# SCH_Ethernet_Based_PCB_Desiging_2026-05-.net
KiCad netlist of a schematic drawn in EasyEDA
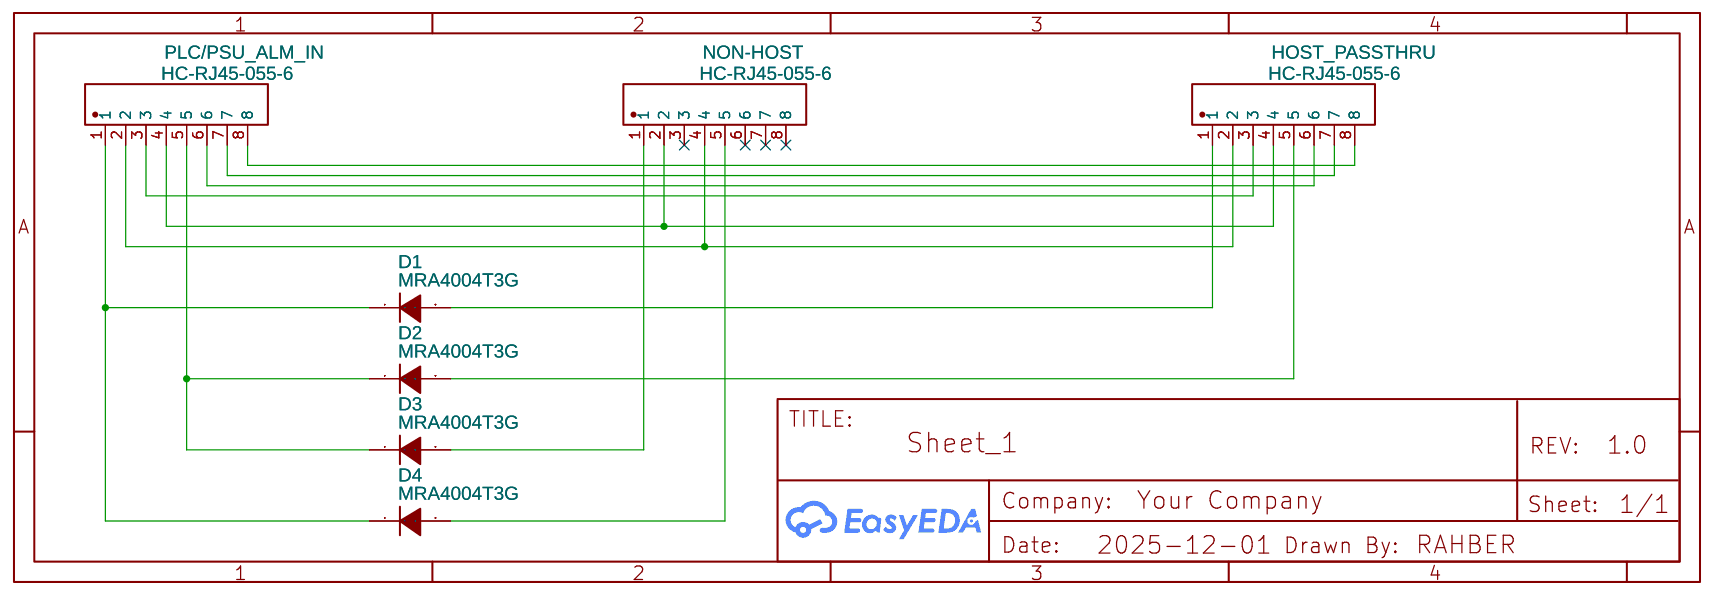
[diagram p0: schematic sheet]

(export (version "E")
  (design (tool "Eeschema 10.0.6"))
  (components
    (comp (ref "D1")
      (value "MRA4004T3G")
      (fields (field (name "Manufacturer") "onsemi(安森美)"))
      (libsource (lib "") (part "MRA4004T3G"))
    )
    (comp (ref "D2")
      (value "MRA4004T3G")
      (fields (field (name "Manufacturer") "onsemi(安森美)"))
      (libsource (lib "") (part "MRA4004T3G"))
    )
    (comp (ref "D3")
      (value "MRA4004T3G")
      (fields (field (name "Manufacturer") "onsemi(安森美)"))
      (libsource (lib "") (part "MRA4004T3G"))
    )
    (comp (ref "D4")
      (value "MRA4004T3G")
      (fields (field (name "Manufacturer") "onsemi(安森美)"))
      (libsource (lib "") (part "MRA4004T3G"))
    )
    (comp (ref "HOST_PASSTHRU")
      (value "HC-RJ45-055-6")
      (fields (field (name "Manufacturer") "HCTL(华灿天禄)"))
      (libsource (lib "") (part "HC-RJ45-055-6"))
    )
    (comp (ref "NON-HOST")
      (value "HC-RJ45-055-6")
      (fields (field (name "Manufacturer") "HCTL(华灿天禄)"))
      (libsource (lib "") (part "HC-RJ45-055-6_2"))
    )
    (comp (ref "PLC/PSU_ALM_IN")
      (value "HC-RJ45-055-6")
      (fields (field (name "Manufacturer") "HCTL(华灿天禄)"))
      (libsource (lib "") (part "HC-RJ45-055-6_1"))
    )
  )
  (nets
    (net (code "1") (name "Net-(D1-+)") (class "Default")
      (node (ref "D1") (pin "2") (pinfunction "+_2") (pintype "unspecified"))
      (node (ref "HOST_PASSTHRU") (pin "1") (pinfunction "1_1") (pintype "unspecified"))
    )
    (net (code "2") (name "Net-(D1--)") (class "Default")
      (node (ref "D1") (pin "1") (pinfunction "-_1") (pintype "unspecified"))
      (node (ref "D4") (pin "1") (pinfunction "-_1") (pintype "unspecified"))
      (node (ref "PLC/PSU_ALM_IN") (pin "1") (pinfunction "1_1") (pintype "unspecified"))
    )
    (net (code "3") (name "Net-(D2-+)") (class "Default")
      (node (ref "D2") (pin "2") (pinfunction "+_2") (pintype "unspecified"))
      (node (ref "HOST_PASSTHRU") (pin "5") (pinfunction "5_5") (pintype "unspecified"))
    )
    (net (code "4") (name "Net-(D2--)") (class "Default")
      (node (ref "D2") (pin "1") (pinfunction "-_1") (pintype "unspecified"))
      (node (ref "D3") (pin "1") (pinfunction "-_1") (pintype "unspecified"))
      (node (ref "PLC/PSU_ALM_IN") (pin "5") (pinfunction "5_5") (pintype "unspecified"))
    )
    (net (code "5") (name "Net-(D3-+)") (class "Default")
      (node (ref "D3") (pin "2") (pinfunction "+_2") (pintype "unspecified"))
      (node (ref "NON-HOST") (pin "1") (pinfunction "1_1") (pintype "unspecified"))
    )
    (net (code "6") (name "Net-(D4-+)") (class "Default")
      (node (ref "D4") (pin "2") (pinfunction "+_2") (pintype "unspecified"))
      (node (ref "NON-HOST") (pin "5") (pinfunction "5_5") (pintype "unspecified"))
    )
    (net (code "7") (name "Net-(HOST_PASSTHRU-Pad2)") (class "Default")
      (node (ref "HOST_PASSTHRU") (pin "2") (pinfunction "2_2") (pintype "unspecified"))
      (node (ref "NON-HOST") (pin "4") (pinfunction "4_4") (pintype "unspecified"))
      (node (ref "PLC/PSU_ALM_IN") (pin "2") (pinfunction "2_2") (pintype "unspecified"))
    )
    (net (code "8") (name "Net-(HOST_PASSTHRU-Pad3)") (class "Default")
      (node (ref "HOST_PASSTHRU") (pin "3") (pinfunction "3_3") (pintype "unspecified"))
      (node (ref "PLC/PSU_ALM_IN") (pin "3") (pinfunction "3_3") (pintype "unspecified"))
    )
    (net (code "9") (name "Net-(HOST_PASSTHRU-Pad4)") (class "Default")
      (node (ref "HOST_PASSTHRU") (pin "4") (pinfunction "4_4") (pintype "unspecified"))
      (node (ref "NON-HOST") (pin "2") (pinfunction "2_2") (pintype "unspecified"))
      (node (ref "PLC/PSU_ALM_IN") (pin "4") (pinfunction "4_4") (pintype "unspecified"))
    )
    (net (code "10") (name "Net-(HOST_PASSTHRU-Pad6)") (class "Default")
      (node (ref "HOST_PASSTHRU") (pin "6") (pinfunction "6_6") (pintype "unspecified"))
      (node (ref "PLC/PSU_ALM_IN") (pin "6") (pinfunction "6_6") (pintype "unspecified"))
    )
    (net (code "11") (name "Net-(HOST_PASSTHRU-Pad7)") (class "Default")
      (node (ref "HOST_PASSTHRU") (pin "7") (pinfunction "7_7") (pintype "unspecified"))
      (node (ref "PLC/PSU_ALM_IN") (pin "7") (pinfunction "7_7") (pintype "unspecified"))
    )
    (net (code "12") (name "Net-(HOST_PASSTHRU-Pad8)") (class "Default")
      (node (ref "HOST_PASSTHRU") (pin "8") (pinfunction "8_8") (pintype "unspecified"))
      (node (ref "PLC/PSU_ALM_IN") (pin "8") (pinfunction "8_8") (pintype "unspecified"))
    )
    (net (code "13") (name "unconnected-(NON-HOST-Pad3)") (class "Default")
      (node (ref "NON-HOST") (pin "3") (pinfunction "3_3") (pintype "unspecified+no_connect"))
    )
    (net (code "14") (name "unconnected-(NON-HOST-Pad6)") (class "Default")
      (node (ref "NON-HOST") (pin "6") (pinfunction "6_6") (pintype "unspecified+no_connect"))
    )
    (net (code "15") (name "unconnected-(NON-HOST-Pad7)") (class "Default")
      (node (ref "NON-HOST") (pin "7") (pinfunction "7_7") (pintype "unspecified+no_connect"))
    )
    (net (code "16") (name "unconnected-(NON-HOST-Pad8)") (class "Default")
      (node (ref "NON-HOST") (pin "8") (pinfunction "8_8") (pintype "unspecified+no_connect"))
    )
  )
)
